# VoltageMeasurement.net
KiCad netlist of a schematic drawn in Altium Designer
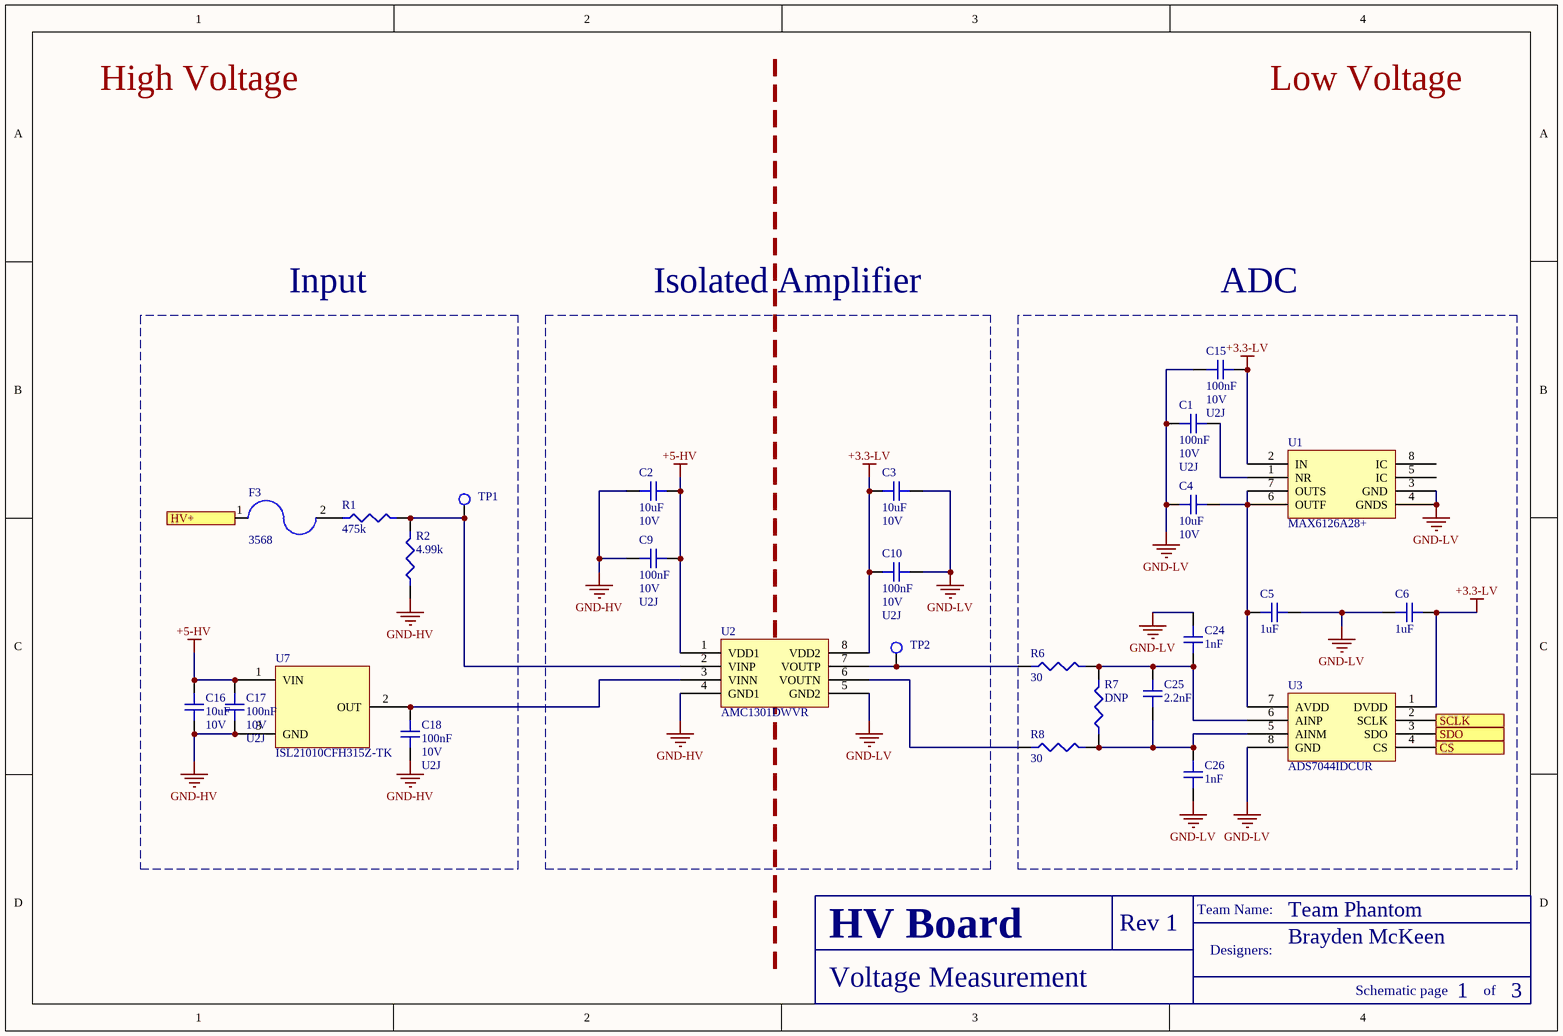
[diagram p0: VoltageMeasurement.SchDoc]

(export (version "E")
  (design (tool "Eeschema 10.0.6"))
  (components
    (comp (ref "C1")
      (value "100nF")
      (footprint "PHANTOM_FOOTPRINTS:C0805")
      (description "CAP MLCC 100nF 10Volts U2J 5%")
      (fields
        (field (name "MANUFACTURER") "Murata")
        (field (name "MANUFACTURER PART NUMBER") "GRM21B7U1A104JA01L")
        (field (name "VOLTAGE RATING") "10V")
        (field (name "DIELECTRIC") "U2J")
      )
      (libsource (lib "PHANTOM_LIBRARY") (part "GRM21B7U1A104JA01L"))
    )
    (comp (ref "C2")
      (value "10uF")
      (footprint "PHANTOM_FOOTPRINTS:C0805")
      (description "CAP CER 10UF 10V X7R 0805")
      (fields
        (field (name "MANUFACTURER") "Murata")
        (field (name "TOLERANCE") "10%")
        (field (name "VOLTAGE RATING") "10V")
      )
      (libsource (lib "PHANTOM_LIBRARY") (part "GCM21BR71A106KE22L"))
    )
    (comp (ref "C3")
      (value "10uF")
      (footprint "PHANTOM_FOOTPRINTS:C0805")
      (description "CAP CER 10UF 10V X7R 0805")
      (fields
        (field (name "MANUFACTURER") "Murata")
        (field (name "TOLERANCE") "10%")
        (field (name "VOLTAGE RATING") "10V")
      )
      (libsource (lib "PHANTOM_LIBRARY") (part "GCM21BR71A106KE22L"))
    )
    (comp (ref "C4")
      (value "10uF")
      (footprint "PHANTOM_FOOTPRINTS:C0805")
      (description "CAP CER 10UF 10V X7R 0805")
      (fields
        (field (name "MANUFACTURER") "Murata")
        (field (name "TOLERANCE") "10%")
        (field (name "VOLTAGE RATING") "10V")
      )
      (libsource (lib "PHANTOM_LIBRARY") (part "GCM21BR71A106KE22L"))
    )
    (comp (ref "C5")
      (value "1uF")
      (footprint "PHANTOM_FOOTPRINTS:C0805")
      (description "CAP CER 1UF 16V X7R 0805")
      (fields
        (field (name "MANUFACTURER") "Murata")
        (field (name "MANUFACTURER PART NUMBER") "GCM21BR71C105KA58K")
      )
      (libsource (lib "PHANTOM_LIBRARY") (part "GCM21BR71C105KA58K"))
    )
    (comp (ref "C6")
      (value "1uF")
      (footprint "PHANTOM_FOOTPRINTS:C0805")
      (description "CAP CER 1UF 16V X7R 0805")
      (fields
        (field (name "MANUFACTURER") "Murata")
        (field (name "MANUFACTURER PART NUMBER") "GCM21BR71C105KA58K")
      )
      (libsource (lib "PHANTOM_LIBRARY") (part "GCM21BR71C105KA58K"))
    )
    (comp (ref "C9")
      (value "100nF")
      (footprint "PHANTOM_FOOTPRINTS:C0805")
      (description "CAP MLCC 100nF 10Volts U2J 5%")
      (fields
        (field (name "MANUFACTURER") "Murata")
        (field (name "MANUFACTURER PART NUMBER") "GRM21B7U1A104JA01L")
        (field (name "VOLTAGE RATING") "10V")
        (field (name "DIELECTRIC") "U2J")
      )
      (libsource (lib "PHANTOM_LIBRARY") (part "GRM21B7U1A104JA01L"))
    )
    (comp (ref "C10")
      (value "100nF")
      (footprint "PHANTOM_FOOTPRINTS:C0805")
      (description "CAP MLCC 100nF 10Volts U2J 5%")
      (fields
        (field (name "MANUFACTURER") "Murata")
        (field (name "MANUFACTURER PART NUMBER") "GRM21B7U1A104JA01L")
        (field (name "VOLTAGE RATING") "10V")
        (field (name "DIELECTRIC") "U2J")
      )
      (libsource (lib "PHANTOM_LIBRARY") (part "GRM21B7U1A104JA01L"))
    )
    (comp (ref "C15")
      (value "100nF")
      (footprint "PHANTOM_FOOTPRINTS:C0805")
      (description "CAP MLCC 100nF 10Volts U2J 5%")
      (fields
        (field (name "MANUFACTURER") "Murata")
        (field (name "MANUFACTURER PART NUMBER") "GRM21B7U1A104JA01L")
        (field (name "VOLTAGE RATING") "10V")
        (field (name "DIELECTRIC") "U2J")
      )
      (libsource (lib "PHANTOM_LIBRARY") (part "GRM21B7U1A104JA01L"))
    )
    (comp (ref "C16")
      (value "10uF")
      (footprint "PHANTOM_FOOTPRINTS:C0805")
      (description "CAP CER 10UF 10V X7R 0805")
      (fields
        (field (name "MANUFACTURER") "Murata")
        (field (name "TOLERANCE") "10%")
        (field (name "VOLTAGE RATING") "10V")
      )
      (libsource (lib "PHANTOM_LIBRARY") (part "GCM21BR71A106KE22L"))
    )
    (comp (ref "C17")
      (value "100nF")
      (footprint "PHANTOM_FOOTPRINTS:C0805")
      (description "CAP MLCC 100nF 10Volts U2J 5%")
      (fields
        (field (name "MANUFACTURER") "Murata")
        (field (name "MANUFACTURER PART NUMBER") "GRM21B7U1A104JA01L")
        (field (name "VOLTAGE RATING") "10V")
        (field (name "DIELECTRIC") "U2J")
      )
      (libsource (lib "PHANTOM_LIBRARY") (part "GRM21B7U1A104JA01L"))
    )
    (comp (ref "C18")
      (value "100nF")
      (footprint "PHANTOM_FOOTPRINTS:C0805")
      (description "CAP MLCC 100nF 10Volts U2J 5%")
      (fields
        (field (name "MANUFACTURER") "Murata")
        (field (name "MANUFACTURER PART NUMBER") "GRM21B7U1A104JA01L")
        (field (name "VOLTAGE RATING") "10V")
        (field (name "DIELECTRIC") "U2J")
      )
      (libsource (lib "PHANTOM_LIBRARY") (part "GRM21B7U1A104JA01L"))
    )
    (comp (ref "C24")
      (value "1nF")
      (footprint "C1206")
      (description "CAP MLCC 1000PF 1KV X7R 1206 Series Comm. Isolation Caps")
      (fields
        (field (name "MANUFACTURER") "Yageo")
        (field (name "MANUFACTURER PART NUMBER") "CC1206KKX7RCBB102")
      )
      (libsource (lib "PHANTOM_LIBRARY") (part "CC1206KKX7RCBB102"))
    )
    (comp (ref "C25")
      (value "2.2nF")
      (footprint "PHANTOM_FOOTPRINTS:C0805")
      (description "CAP CER 2200PF 250V X7R 0805")
      (fields
        (field (name "MANUFACTURER") "Murata")
        (field (name "MANUFACTURER PART NUMBER") "GCJ21AR72E222KXJ1D")
      )
      (libsource (lib "PHANTOM_LIBRARY") (part "GCJ21AR72E222KXJ1D"))
    )
    (comp (ref "C26")
      (value "1nF")
      (footprint "C1206")
      (description "CAP MLCC 1000PF 1KV X7R 1206 Series Comm. Isolation Caps")
      (fields
        (field (name "MANUFACTURER") "Yageo")
        (field (name "MANUFACTURER PART NUMBER") "CC1206KKX7RCBB102")
      )
      (libsource (lib "PHANTOM_LIBRARY") (part "CC1206KKX7RCBB102"))
    )
    (comp (ref "F3")
      (value "3568")
      (footprint "FUSE_MINI_HOLDER")
      (description "FUSE HOLDER MINI AUTO PC")
      (fields (field (name "MANUFACTURER") "Keystone Electronics") (field (name "VOLTAGE") "500V"))
      (libsource (lib "PHANTOM_LIBRARY") (part "3568"))
    )
    (comp (ref "R1")
      (value "475k")
      (footprint "Res-475k-RNF18FTD475K")
      (description "RES 475K OHM 1/8W 1% AXIAL")
      (fields (field (name "TOLERANCE") "1%") (field (name "POWER") "0.125W"))
      (libsource (lib "PHANTOM_LIBRARY") (part "RNF18FTD475K"))
    )
    (comp (ref "R2")
      (value "4.99k")
      (footprint "R0805")
      (description "RES 4.99K OHM 0.1% 1/8W 0805")
      (fields (field (name "TOLERANCE") "0.1%") (field (name "POWER") "0.125W"))
      (libsource (lib "PHANTOM_LIBRARY") (part "ERA-6AEB4991V"))
    )
    (comp (ref "R6")
      (value "30")
      (footprint "R0805")
      (description "RES SMD 30 OHM 1% 1/8W 0805")
      (fields
        (field (name "MANUFACTURER") "Panasonic")
        (field (name "MANUFACTURER PART NUMBER") "ERJ-6ENF30R0V")
      )
      (libsource (lib "PHANTOM_LIBRARY") (part "ERJ-6ENF30R0V"))
    )
    (comp (ref "R7")
      (value "DNP")
      (footprint "R0805")
      (description "RES 0805 DNP")
      (libsource (lib "PHANTOM_LIBRARY") (part "DNP"))
    )
    (comp (ref "R8")
      (value "30")
      (footprint "R0805")
      (description "RES SMD 30 OHM 1% 1/8W 0805")
      (fields
        (field (name "MANUFACTURER") "Panasonic")
        (field (name "MANUFACTURER PART NUMBER") "ERJ-6ENF30R0V")
      )
      (libsource (lib "PHANTOM_LIBRARY") (part "ERJ-6ENF30R0V"))
    )
    (comp (ref "TP1")
      (value "5015")
      (footprint "TP_HOOK")
      (description "TEST POINT, PCB, SMT")
      (fields (field (name "MANUFACTURER") "Keystone Electronics"))
      (libsource (lib "PHANTOM_LIBRARY") (part "5015"))
    )
    (comp (ref "TP2")
      (value "5015")
      (footprint "TP_HOOK")
      (description "TEST POINT, PCB, SMT")
      (fields (field (name "MANUFACTURER") "Keystone Electronics"))
      (libsource (lib "PHANTOM_LIBRARY") (part "5015"))
    )
    (comp (ref "U1")
      (value "MAX6126A28+")
      (footprint "REF5030IDGKT")
      (description "IC VREF SERIES 0.06% 8UMAX")
      (fields (field (name "MANUFACTURER") "Maxim Integrated"))
      (libsource (lib "PHANTOM_LIBRARY") (part "MAX6126A28+"))
    )
    (comp (ref "U2")
      (value "AMC1301DWVR")
      (footprint "AMC1301DWVR")
      (description "IC OPAMP ISOLATION 1 CIRC 8 SOIC")
      (fields (field (name "MANUFACTURER") "Texas Instruments"))
      (libsource (lib "PHANTOM_LIBRARY") (part "AMC1301DWVR"))
    )
    (comp (ref "U3")
      (value "ADS7044IDCUR")
      (footprint "ADS7044IDCUR")
      (description "IC ADC 12BIT SAR 8VSSOP")
      (fields (field (name "MANUFACTURER") "Texas Instruments"))
      (libsource (lib "PHANTOM_LIBRARY") (part "ADS7044IDCUR"))
    )
    (comp (ref "U7")
      (value "ISL21010CFH315Z-TK")
      (footprint "ISL21010CFH315Z-TK")
      (description "IC VREF SERIES 0.2% SOT23-3")
      (libsource (lib "PHANTOM_LIBRARY") (part "ISL21010CFH315Z-TK"))
    )
  )
  (nets
    (net (code "1") (name "+3.3-LV") (class "Default")
      (node (ref "C10") (pin "1") (pinfunction "1_1") (pintype "passive"))
      (node (ref "C15") (pin "2") (pinfunction "2_2") (pintype "passive"))
      (node (ref "C3") (pin "1") (pinfunction "1_1") (pintype "passive"))
      (node (ref "C6") (pin "2") (pinfunction "2_2") (pintype "passive"))
      (node (ref "U1") (pin "2") (pinfunction "IN_2") (pintype "passive"))
      (node (ref "U2") (pin "8") (pinfunction "VDD2_8") (pintype "passive"))
      (node (ref "U3") (pin "1") (pinfunction "DVDD_1") (pintype "passive"))
    )
    (net (code "2") (name "+5-HV") (class "Default")
      (node (ref "C16") (pin "2") (pinfunction "2_2") (pintype "passive"))
      (node (ref "C17") (pin "2") (pinfunction "2_2") (pintype "passive"))
      (node (ref "C2") (pin "1") (pinfunction "1_1") (pintype "passive"))
      (node (ref "C9") (pin "1") (pinfunction "1_1") (pintype "passive"))
      (node (ref "U2") (pin "1") (pinfunction "VDD1_1") (pintype "passive"))
      (node (ref "U7") (pin "1") (pinfunction "VIN_1") (pintype "passive"))
    )
    (net (code "3") (name "/CS") (class "Default")
      (node (ref "U3") (pin "4") (pinfunction "CS_4") (pintype "passive"))
    )
    (net (code "4") (name "/HV+") (class "Default")
      (node (ref "F3") (pin "1") (pinfunction "1_1") (pintype "passive"))
    )
    (net (code "5") (name "/SCLK") (class "Default")
      (node (ref "U3") (pin "2") (pinfunction "SCLK_2") (pintype "passive"))
    )
    (net (code "6") (name "/SDO") (class "Default")
      (node (ref "U3") (pin "3") (pinfunction "SDO_3") (pintype "passive"))
    )
    (net (code "7") (name "GND-HV") (class "Default")
      (node (ref "C16") (pin "1") (pinfunction "1_1") (pintype "passive"))
      (node (ref "C17") (pin "1") (pinfunction "1_1") (pintype "passive"))
      (node (ref "C18") (pin "1") (pinfunction "1_1") (pintype "passive"))
      (node (ref "C2") (pin "2") (pinfunction "2_2") (pintype "passive"))
      (node (ref "C9") (pin "2") (pinfunction "2_2") (pintype "passive"))
      (node (ref "R2") (pin "1") (pinfunction "1_1") (pintype "passive"))
      (node (ref "U2") (pin "4") (pinfunction "GND1_4") (pintype "passive"))
      (node (ref "U7") (pin "3") (pinfunction "GND_3") (pintype "passive"))
    )
    (net (code "8") (name "GND-LV") (class "Default")
      (node (ref "C1") (pin "1") (pinfunction "1_1") (pintype "passive"))
      (node (ref "C10") (pin "2") (pinfunction "2_2") (pintype "passive"))
      (node (ref "C15") (pin "1") (pinfunction "1_1") (pintype "passive"))
      (node (ref "C24") (pin "2") (pinfunction "2_2") (pintype "passive"))
      (node (ref "C26") (pin "1") (pinfunction "1_1") (pintype "passive"))
      (node (ref "C3") (pin "2") (pinfunction "2_2") (pintype "passive"))
      (node (ref "C4") (pin "1") (pinfunction "1_1") (pintype "passive"))
      (node (ref "C5") (pin "2") (pinfunction "2_2") (pintype "passive"))
      (node (ref "C6") (pin "1") (pinfunction "1_1") (pintype "passive"))
      (node (ref "U1") (pin "3") (pinfunction "GND_3") (pintype "passive"))
      (node (ref "U1") (pin "4") (pinfunction "GNDS_4") (pintype "passive"))
      (node (ref "U2") (pin "5") (pinfunction "GND2_5") (pintype "passive"))
      (node (ref "U3") (pin "8") (pinfunction "GND_8") (pintype "passive"))
    )
    (net (code "9") (name "Net-(F3-Pad2)") (class "Default")
      (node (ref "F3") (pin "2") (pinfunction "2_2") (pintype "passive"))
      (node (ref "R1") (pin "1") (pinfunction "1_1") (pintype "passive"))
    )
    (net (code "10") (name "Net-(U1-NR)") (class "Default")
      (node (ref "C1") (pin "2") (pinfunction "2_2") (pintype "passive"))
      (node (ref "U1") (pin "1") (pinfunction "NR_1") (pintype "passive"))
    )
    (net (code "11") (name "Net-(U1-OUTF)") (class "Default")
      (node (ref "C4") (pin "2") (pinfunction "2_2") (pintype "passive"))
      (node (ref "C5") (pin "1") (pinfunction "1_1") (pintype "passive"))
      (node (ref "U1") (pin "6") (pinfunction "OUTF_6") (pintype "passive"))
      (node (ref "U1") (pin "7") (pinfunction "OUTS_7") (pintype "passive"))
      (node (ref "U3") (pin "7") (pinfunction "AVDD_7") (pintype "passive"))
    )
    (net (code "12") (name "Net-(U2-VINN)") (class "Default")
      (node (ref "C18") (pin "2") (pinfunction "2_2") (pintype "passive"))
      (node (ref "U2") (pin "3") (pinfunction "VINN_3") (pintype "passive"))
      (node (ref "U7") (pin "2") (pinfunction "OUT_2") (pintype "passive"))
    )
    (net (code "13") (name "Net-(U2-VINP)") (class "Default")
      (node (ref "R1") (pin "2") (pinfunction "2_2") (pintype "passive"))
      (node (ref "R2") (pin "2") (pinfunction "2_2") (pintype "passive"))
      (node (ref "TP1") (pin "1") (pinfunction "1_1") (pintype "passive"))
      (node (ref "U2") (pin "2") (pinfunction "VINP_2") (pintype "passive"))
    )
    (net (code "14") (name "Net-(U2-VOUTN)") (class "Default")
      (node (ref "R8") (pin "1") (pinfunction "1_1") (pintype "passive"))
      (node (ref "U2") (pin "6") (pinfunction "VOUTN_6") (pintype "passive"))
    )
    (net (code "15") (name "Net-(U2-VOUTP)") (class "Default")
      (node (ref "R6") (pin "1") (pinfunction "1_1") (pintype "passive"))
      (node (ref "TP2") (pin "1") (pinfunction "1_1") (pintype "passive"))
      (node (ref "U2") (pin "7") (pinfunction "VOUTP_7") (pintype "passive"))
    )
    (net (code "16") (name "Net-(U3-AINM)") (class "Default")
      (node (ref "C25") (pin "1") (pinfunction "1_1") (pintype "passive"))
      (node (ref "C26") (pin "2") (pinfunction "2_2") (pintype "passive"))
      (node (ref "R7") (pin "1") (pinfunction "1_1") (pintype "passive"))
      (node (ref "R8") (pin "2") (pinfunction "2_2") (pintype "passive"))
      (node (ref "U3") (pin "5") (pinfunction "AINM_5") (pintype "passive"))
    )
    (net (code "17") (name "Net-(U3-AINP)") (class "Default")
      (node (ref "C24") (pin "1") (pinfunction "1_1") (pintype "passive"))
      (node (ref "C25") (pin "2") (pinfunction "2_2") (pintype "passive"))
      (node (ref "R6") (pin "2") (pinfunction "2_2") (pintype "passive"))
      (node (ref "R7") (pin "2") (pinfunction "2_2") (pintype "passive"))
      (node (ref "U3") (pin "6") (pinfunction "AINP_6") (pintype "passive"))
    )
    (net (code "18") (name "unconnected-(U1-IC-Pad5)") (class "Default")
      (node (ref "U1") (pin "5") (pinfunction "IC_5") (pintype "passive"))
    )
    (net (code "19") (name "unconnected-(U1-IC-Pad8)") (class "Default")
      (node (ref "U1") (pin "8") (pinfunction "IC_8") (pintype "passive"))
    )
  )
)
